# dual_encoder_i2c_revA.net
KiCad netlist of a schematic drawn in EAGLE
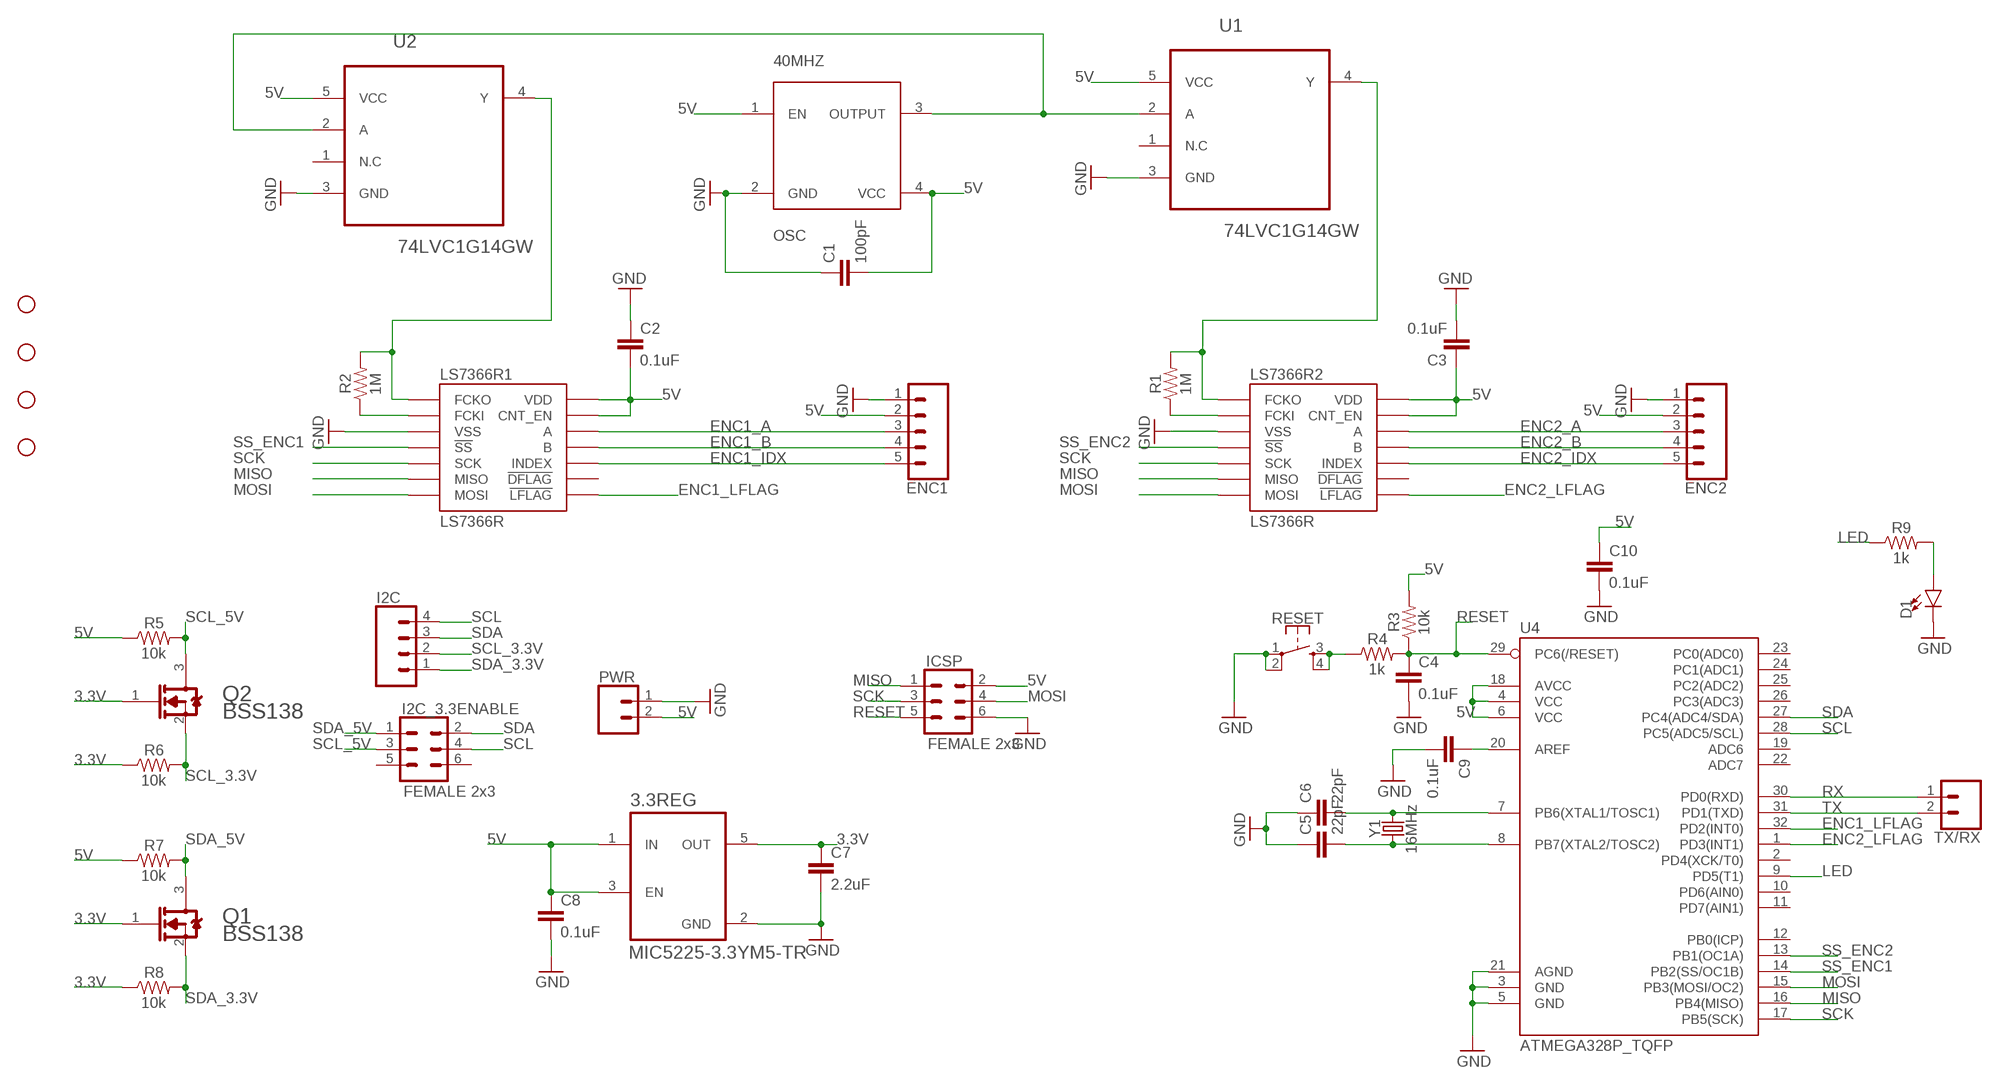
[diagram p0: schematic, sheet 1]

(export (version "E")
  (design (tool "Eeschema 10.0.6"))
  (components
    (comp (ref "3.3REG")
      (value "MIC5225-3.3YM5-TR")
      (footprint "eagle-import:SOT95P280X145-5N")
      (fields (field (name "MF") "Microchip"))
      (libsource (lib "eagle-import") (part "MIC5225-3.3YM5-TR"))
    )
    (comp (ref "40MHZ")
      (value "OSC")
      (footprint "eagle-import:CB3OSCILLATOR")
      (libsource (lib "eagle-import") (part "OSC"))
    )
    (comp (ref "C1")
      (value "100pF")
      (footprint "eagle-import:0603")
      (libsource (lib "eagle-import") (part "100PF-0603-50V-5%"))
    )
    (comp (ref "C2")
      (value "0.1uF")
      (footprint "eagle-import:0603")
      (libsource (lib "eagle-import") (part "0.1UF-0603-25V-5%"))
    )
    (comp (ref "C3")
      (value "0.1uF")
      (footprint "eagle-import:0603")
      (libsource (lib "eagle-import") (part "0.1UF-0603-25V-5%"))
    )
    (comp (ref "C4")
      (value "0.1uF")
      (footprint "eagle-import:0603")
      (libsource (lib "eagle-import") (part "0.1UF-0603-25V-5%"))
    )
    (comp (ref "C5")
      (value "22pF")
      (footprint "eagle-import:0603")
      (libsource (lib "eagle-import") (part "22PF-0603-50V-5%"))
    )
    (comp (ref "C6")
      (value "22pF")
      (footprint "eagle-import:0603")
      (libsource (lib "eagle-import") (part "22PF-0603-50V-5%"))
    )
    (comp (ref "C7")
      (value "2.2uF")
      (footprint "eagle-import:0603")
      (libsource (lib "eagle-import") (part "2.2UF-0603-10V-20%"))
    )
    (comp (ref "C8")
      (value "0.1uF")
      (footprint "eagle-import:0603")
      (libsource (lib "eagle-import") (part "0.1UF-0603-25V-5%"))
    )
    (comp (ref "C9")
      (value "0.1uF")
      (footprint "eagle-import:0603")
      (libsource (lib "eagle-import") (part "0.1UF-0603-25V-5%"))
    )
    (comp (ref "C10")
      (value "0.1uF")
      (footprint "eagle-import:0603")
      (libsource (lib "eagle-import") (part "0.1UF-0603-25V-5%"))
    )
    (comp (ref "D1")
      (value "LED0603")
      (footprint "eagle-import:LED-0603")
      (libsource (lib "eagle-import") (part "LED0603"))
    )
    (comp (ref "ENC1")
      (value "CONN_05")
      (footprint "eagle-import:1X05")
      (libsource (lib "eagle-import") (part "CONN_05"))
    )
    (comp (ref "ENC2")
      (value "CONN_05")
      (footprint "eagle-import:1X05")
      (libsource (lib "eagle-import") (part "CONN_05"))
    )
    (comp (ref "H1")
      (value "STAND-OFF")
      (footprint "eagle-import:STAND-OFF")
      (libsource (lib "eagle-import") (part "STAND-OFF"))
    )
    (comp (ref "H2")
      (value "STAND-OFF")
      (footprint "eagle-import:STAND-OFF")
      (libsource (lib "eagle-import") (part "STAND-OFF"))
    )
    (comp (ref "H3")
      (value "STAND-OFF")
      (footprint "eagle-import:STAND-OFF")
      (libsource (lib "eagle-import") (part "STAND-OFF"))
    )
    (comp (ref "H4")
      (value "STAND-OFF")
      (footprint "eagle-import:STAND-OFF")
      (libsource (lib "eagle-import") (part "STAND-OFF"))
    )
    (comp (ref "I2C")
      (value "CONN_04")
      (footprint "eagle-import:1X04")
      (libsource (lib "eagle-import") (part "CONN_04"))
    )
    (comp (ref "I2C_3.3ENABLE")
      (value "FEMALE 2x3")
      (footprint "eagle-import:2X3")
      (libsource (lib "eagle-import") (part "CONN_03X2FEMALE"))
    )
    (comp (ref "ICSP")
      (value "FEMALE 2x3")
      (footprint "eagle-import:2X3")
      (libsource (lib "eagle-import") (part "CONN_03X2FEMALE"))
    )
    (comp (ref "LS7366R1")
      (value "LS7366R")
      (footprint "eagle-import:SOIC14")
      (fields (field (name "MF") "LSI"))
      (libsource (lib "eagle-import") (part "LS7366R"))
    )
    (comp (ref "LS7366R2")
      (value "LS7366R")
      (footprint "eagle-import:SOIC14")
      (fields (field (name "MF") "LSI"))
      (libsource (lib "eagle-import") (part "LS7366R"))
    )
    (comp (ref "PWR")
      (value "CONN_02-JST-2MM-SMT")
      (footprint "eagle-import:JST-2-SMD")
      (libsource (lib "eagle-import") (part "CONN_02-JST-2MM-SMT"))
    )
    (comp (ref "Q1")
      (value "ON_SEMI_BSS138ON_SEMI_BSS138_0_0")
      (footprint "eagle-import:ON_SEMI_BSS138_0")
      (fields
        (field (name "DIGIKEY_PART_NUMBER") "BSS138CT-ND")
        (field (name "MF") "ON Semi")
        (field (name "MOUSER_PART_NUMBER") "512-BSS138")
      )
      (libsource (lib "eagle-import") (part "ON_SEMI_BSS138ON_SEMI_BSS138_0_0"))
    )
    (comp (ref "Q2")
      (value "ON_SEMI_BSS138ON_SEMI_BSS138_0_0")
      (footprint "eagle-import:ON_SEMI_BSS138_0")
      (fields
        (field (name "DIGIKEY_PART_NUMBER") "BSS138CT-ND")
        (field (name "MF") "ON Semi")
        (field (name "MOUSER_PART_NUMBER") "512-BSS138")
      )
      (libsource (lib "eagle-import") (part "ON_SEMI_BSS138ON_SEMI_BSS138_0_0"))
    )
    (comp (ref "R1")
      (value "1M")
      (footprint "eagle-import:0603")
      (libsource (lib "eagle-import") (part "1MOHM-0603-1/4W-5%"))
    )
    (comp (ref "R2")
      (value "1M")
      (footprint "eagle-import:0603")
      (libsource (lib "eagle-import") (part "1MOHM-0603-1/4W-5%"))
    )
    (comp (ref "R3")
      (value "10k")
      (footprint "eagle-import:0603")
      (libsource (lib "eagle-import") (part "10KOHM-0603-1/10W-1%"))
    )
    (comp (ref "R4")
      (value "1k")
      (footprint "eagle-import:0603")
      (libsource (lib "eagle-import") (part "1KOHM-0603-1/10W-1%"))
    )
    (comp (ref "R5")
      (value "10k")
      (footprint "eagle-import:0603")
      (libsource (lib "eagle-import") (part "10KOHM-0603-1/10W-1%"))
    )
    (comp (ref "R6")
      (value "10k")
      (footprint "eagle-import:0603")
      (libsource (lib "eagle-import") (part "10KOHM-0603-1/10W-1%"))
    )
    (comp (ref "R7")
      (value "10k")
      (footprint "eagle-import:0603")
      (libsource (lib "eagle-import") (part "10KOHM-0603-1/10W-1%"))
    )
    (comp (ref "R8")
      (value "10k")
      (footprint "eagle-import:0603")
      (libsource (lib "eagle-import") (part "10KOHM-0603-1/10W-1%"))
    )
    (comp (ref "R9")
      (value "1k")
      (footprint "eagle-import:0603")
      (libsource (lib "eagle-import") (part "1KOHM-0603-1/10W-1%"))
    )
    (comp (ref "RESET")
      (value "MOMENTARY-SWITCH-SPST-2-SMD-5.2MM")
      (footprint "eagle-import:TACTILE_SWITCH_SMD_5.2MM")
      (libsource (lib "eagle-import") (part "MOMENTARY-SWITCH-SPST-2-SMD-5.2MM"))
    )
    (comp (ref "TX/RX")
      (value "CONN_02")
      (footprint "eagle-import:1X02")
      (libsource (lib "eagle-import") (part "CONN_02"))
    )
    (comp (ref "U1")
      (value "74LVC1G14GW")
      (footprint "eagle-import:SOT65P210X110-5N")
      (fields (field (name "MF") "NXP Semiconductors"))
      (libsource (lib "eagle-import") (part "74LVC1G14GW"))
    )
    (comp (ref "U2")
      (value "74LVC1G14GW")
      (footprint "eagle-import:SOT65P210X110-5N")
      (fields (field (name "MF") "NXP Semiconductors"))
      (libsource (lib "eagle-import") (part "74LVC1G14GW"))
    )
    (comp (ref "U4")
      (value "ATMEGA328P_TQFP")
      (footprint "eagle-import:TQFP32-08")
      (libsource (lib "eagle-import") (part "ATMEGA328P_TQFP"))
    )
    (comp (ref "Y1")
      (value "16MHz")
      (footprint "eagle-import:HC49US")
      (libsource (lib "eagle-import") (part "CRYSTAL-16MHZPTH-HC49US"))
    )
  )
  (nets
    (net (code "1") (name "/3.3V") (class "Default")
      (node (ref "3.3REG") (pin "5") (pinfunction "OUT_5") (pintype "output"))
      (node (ref "C7") (pin "1") (pinfunction "1_1") (pintype "passive"))
      (node (ref "Q1") (pin "1") (pinfunction "G_1") (pintype "bidirectional"))
      (node (ref "Q2") (pin "1") (pinfunction "G_1") (pintype "bidirectional"))
      (node (ref "R6") (pin "1") (pinfunction "1_1") (pintype "passive"))
      (node (ref "R8") (pin "1") (pinfunction "1_1") (pintype "passive"))
    )
    (net (code "2") (name "/5V") (class "Default")
      (node (ref "3.3REG") (pin "1") (pinfunction "IN_1") (pintype "input"))
      (node (ref "3.3REG") (pin "3") (pinfunction "EN_3") (pintype "input"))
      (node (ref "40MHZ") (pin "1") (pinfunction "EN_1") (pintype "input"))
      (node (ref "40MHZ") (pin "4") (pinfunction "VCC_4") (pintype "input"))
      (node (ref "C1") (pin "2") (pinfunction "2_2") (pintype "passive"))
      (node (ref "C10") (pin "1") (pinfunction "1_1") (pintype "passive"))
      (node (ref "C2") (pin "2") (pinfunction "2_2") (pintype "passive"))
      (node (ref "C3") (pin "1") (pinfunction "1_1") (pintype "passive"))
      (node (ref "C8") (pin "1") (pinfunction "1_1") (pintype "passive"))
      (node (ref "ENC1") (pin "2") (pinfunction "2_2") (pintype "passive"))
      (node (ref "ENC2") (pin "2") (pinfunction "2_2") (pintype "passive"))
      (node (ref "ICSP") (pin "2") (pinfunction "2_2") (pintype "bidirectional"))
      (node (ref "LS7366R1") (pin "13") (pinfunction "CNT_EN_13") (pintype "bidirectional"))
      (node (ref "LS7366R1") (pin "14") (pinfunction "VDD_14") (pintype "bidirectional"))
      (node (ref "LS7366R2") (pin "13") (pinfunction "CNT_EN_13") (pintype "bidirectional"))
      (node (ref "LS7366R2") (pin "14") (pinfunction "VDD_14") (pintype "bidirectional"))
      (node (ref "PWR") (pin "2") (pinfunction "1_2") (pintype "passive"))
      (node (ref "R3") (pin "2") (pinfunction "2_2") (pintype "passive"))
      (node (ref "R5") (pin "1") (pinfunction "1_1") (pintype "passive"))
      (node (ref "R7") (pin "1") (pinfunction "1_1") (pintype "passive"))
      (node (ref "U1") (pin "5") (pinfunction "VCC_5") (pintype "power_in"))
      (node (ref "U2") (pin "5") (pinfunction "VCC_5") (pintype "power_in"))
      (node (ref "U4") (pin "18") (pinfunction "AVCC_18") (pintype "bidirectional"))
      (node (ref "U4") (pin "4") (pinfunction "VCC_4") (pintype "bidirectional"))
      (node (ref "U4") (pin "6") (pinfunction "VCC_6") (pintype "bidirectional"))
    )
    (net (code "3") (name "/ENC1_A") (class "Default")
      (node (ref "ENC1") (pin "3") (pinfunction "3_3") (pintype "passive"))
      (node (ref "LS7366R1") (pin "12") (pinfunction "A_12") (pintype "bidirectional"))
    )
    (net (code "4") (name "/ENC1_B") (class "Default")
      (node (ref "ENC1") (pin "4") (pinfunction "4_4") (pintype "passive"))
      (node (ref "LS7366R1") (pin "11") (pinfunction "B_11") (pintype "bidirectional"))
    )
    (net (code "5") (name "/ENC1_IDX") (class "Default")
      (node (ref "ENC1") (pin "5") (pinfunction "5_5") (pintype "passive"))
      (node (ref "LS7366R1") (pin "10") (pinfunction "INDEX_10") (pintype "bidirectional"))
    )
    (net (code "6") (name "/ENC1_LFLAG") (class "Default")
      (node (ref "LS7366R1") (pin "8") (pinfunction "~{LFLAG}_8") (pintype "bidirectional"))
      (node (ref "U4") (pin "32") (pinfunction "PD2(INT0)_32") (pintype "bidirectional"))
    )
    (net (code "7") (name "/ENC2_A") (class "Default")
      (node (ref "ENC2") (pin "3") (pinfunction "3_3") (pintype "passive"))
      (node (ref "LS7366R2") (pin "12") (pinfunction "A_12") (pintype "bidirectional"))
    )
    (net (code "8") (name "/ENC2_B") (class "Default")
      (node (ref "ENC2") (pin "4") (pinfunction "4_4") (pintype "passive"))
      (node (ref "LS7366R2") (pin "11") (pinfunction "B_11") (pintype "bidirectional"))
    )
    (net (code "9") (name "/ENC2_IDX") (class "Default")
      (node (ref "ENC2") (pin "5") (pinfunction "5_5") (pintype "passive"))
      (node (ref "LS7366R2") (pin "10") (pinfunction "INDEX_10") (pintype "bidirectional"))
    )
    (net (code "10") (name "/ENC2_LFLAG") (class "Default")
      (node (ref "LS7366R2") (pin "8") (pinfunction "~{LFLAG}_8") (pintype "bidirectional"))
      (node (ref "U4") (pin "1") (pinfunction "PD3(INT1)_1") (pintype "bidirectional"))
    )
    (net (code "11") (name "/LED") (class "Default")
      (node (ref "R9") (pin "1") (pinfunction "1_1") (pintype "passive"))
      (node (ref "U4") (pin "9") (pinfunction "PD5(T1)_9") (pintype "bidirectional"))
    )
    (net (code "12") (name "/MISO") (class "Default")
      (node (ref "ICSP") (pin "1") (pinfunction "1_1") (pintype "bidirectional"))
      (node (ref "LS7366R1") (pin "6") (pinfunction "MISO_6") (pintype "bidirectional"))
      (node (ref "LS7366R2") (pin "6") (pinfunction "MISO_6") (pintype "bidirectional"))
      (node (ref "U4") (pin "16") (pinfunction "PB4(MISO)_16") (pintype "bidirectional"))
    )
    (net (code "13") (name "/MOSI") (class "Default")
      (node (ref "ICSP") (pin "4") (pinfunction "4_4") (pintype "bidirectional"))
      (node (ref "LS7366R1") (pin "7") (pinfunction "MOSI_7") (pintype "bidirectional"))
      (node (ref "LS7366R2") (pin "7") (pinfunction "MOSI_7") (pintype "bidirectional"))
      (node (ref "U4") (pin "15") (pinfunction "PB3(MOSI/OC2)_15") (pintype "bidirectional"))
    )
    (net (code "14") (name "/RESET") (class "Default")
      (node (ref "C4") (pin "1") (pinfunction "1_1") (pintype "passive"))
      (node (ref "ICSP") (pin "5") (pinfunction "5_5") (pintype "bidirectional"))
      (node (ref "R3") (pin "1") (pinfunction "1_1") (pintype "passive"))
      (node (ref "R4") (pin "2") (pinfunction "2_2") (pintype "passive"))
      (node (ref "U4") (pin "29") (pinfunction "PC6(/RESET)_29") (pintype "bidirectional"))
    )
    (net (code "15") (name "/RX") (class "Default")
      (node (ref "TX/RX") (pin "1") (pinfunction "1_1") (pintype "passive"))
      (node (ref "U4") (pin "30") (pinfunction "PD0(RXD)_30") (pintype "bidirectional"))
    )
    (net (code "16") (name "/SCK") (class "Default")
      (node (ref "ICSP") (pin "3") (pinfunction "3_3") (pintype "bidirectional"))
      (node (ref "LS7366R1") (pin "5") (pinfunction "SCK_5") (pintype "bidirectional"))
      (node (ref "LS7366R2") (pin "5") (pinfunction "SCK_5") (pintype "bidirectional"))
      (node (ref "U4") (pin "17") (pinfunction "PB5(SCK)_17") (pintype "bidirectional"))
    )
    (net (code "17") (name "/SCL") (class "Default")
      (node (ref "I2C") (pin "4") (pinfunction "4_4") (pintype "passive"))
      (node (ref "I2C_3.3ENABLE") (pin "4") (pinfunction "4_4") (pintype "bidirectional"))
      (node (ref "U4") (pin "28") (pinfunction "PC5(ADC5/SCL)_28") (pintype "bidirectional"))
    )
    (net (code "18") (name "/SCL_3.3V") (class "Default")
      (node (ref "I2C") (pin "2") (pinfunction "2_2") (pintype "passive"))
      (node (ref "Q2") (pin "2") (pinfunction "S_2") (pintype "bidirectional"))
      (node (ref "R6") (pin "2") (pinfunction "2_2") (pintype "passive"))
    )
    (net (code "19") (name "/SCL_5V") (class "Default")
      (node (ref "I2C_3.3ENABLE") (pin "3") (pinfunction "3_3") (pintype "bidirectional"))
      (node (ref "Q2") (pin "3") (pinfunction "D_3") (pintype "bidirectional"))
      (node (ref "R5") (pin "2") (pinfunction "2_2") (pintype "passive"))
    )
    (net (code "20") (name "/SDA") (class "Default")
      (node (ref "I2C") (pin "3") (pinfunction "3_3") (pintype "passive"))
      (node (ref "I2C_3.3ENABLE") (pin "2") (pinfunction "2_2") (pintype "bidirectional"))
      (node (ref "U4") (pin "27") (pinfunction "PC4(ADC4/SDA)_27") (pintype "bidirectional"))
    )
    (net (code "21") (name "/SDA_3.3V") (class "Default")
      (node (ref "I2C") (pin "1") (pinfunction "1_1") (pintype "passive"))
      (node (ref "Q1") (pin "2") (pinfunction "S_2") (pintype "bidirectional"))
      (node (ref "R8") (pin "2") (pinfunction "2_2") (pintype "passive"))
    )
    (net (code "22") (name "/SDA_5V") (class "Default")
      (node (ref "I2C_3.3ENABLE") (pin "1") (pinfunction "1_1") (pintype "bidirectional"))
      (node (ref "Q1") (pin "3") (pinfunction "D_3") (pintype "bidirectional"))
      (node (ref "R7") (pin "2") (pinfunction "2_2") (pintype "passive"))
    )
    (net (code "23") (name "/SS_ENC1") (class "Default")
      (node (ref "LS7366R1") (pin "4") (pinfunction "~{SS}_4") (pintype "bidirectional"))
      (node (ref "U4") (pin "14") (pinfunction "PB2(SS/OC1B)_14") (pintype "bidirectional"))
    )
    (net (code "24") (name "/SS_ENC2") (class "Default")
      (node (ref "LS7366R2") (pin "4") (pinfunction "~{SS}_4") (pintype "bidirectional"))
      (node (ref "U4") (pin "13") (pinfunction "PB1(OC1A)_13") (pintype "bidirectional"))
    )
    (net (code "25") (name "/TX") (class "Default")
      (node (ref "TX/RX") (pin "2") (pinfunction "2_2") (pintype "passive"))
      (node (ref "U4") (pin "31") (pinfunction "PD1(TXD)_31") (pintype "bidirectional"))
    )
    (net (code "26") (name "GND") (class "Default")
      (node (ref "3.3REG") (pin "2") (pinfunction "GND_2") (pintype "power_in"))
      (node (ref "40MHZ") (pin "2") (pinfunction "GND_2") (pintype "input"))
      (node (ref "C1") (pin "1") (pinfunction "1_1") (pintype "passive"))
      (node (ref "C10") (pin "2") (pinfunction "2_2") (pintype "passive"))
      (node (ref "C2") (pin "1") (pinfunction "1_1") (pintype "passive"))
      (node (ref "C3") (pin "2") (pinfunction "2_2") (pintype "passive"))
      (node (ref "C4") (pin "2") (pinfunction "2_2") (pintype "passive"))
      (node (ref "C5") (pin "1") (pinfunction "1_1") (pintype "passive"))
      (node (ref "C6") (pin "1") (pinfunction "1_1") (pintype "passive"))
      (node (ref "C7") (pin "2") (pinfunction "2_2") (pintype "passive"))
      (node (ref "C8") (pin "2") (pinfunction "2_2") (pintype "passive"))
      (node (ref "C9") (pin "2") (pinfunction "2_2") (pintype "passive"))
      (node (ref "D1") (pin "C") (pinfunction "C_C") (pintype "passive"))
      (node (ref "ENC1") (pin "1") (pinfunction "1_1") (pintype "passive"))
      (node (ref "ENC2") (pin "1") (pinfunction "1_1") (pintype "passive"))
      (node (ref "ICSP") (pin "6") (pinfunction "6_6") (pintype "bidirectional"))
      (node (ref "LS7366R1") (pin "3") (pinfunction "VSS_3") (pintype "bidirectional"))
      (node (ref "LS7366R2") (pin "3") (pinfunction "VSS_3") (pintype "bidirectional"))
      (node (ref "PWR") (pin "1") (pinfunction "2_1") (pintype "passive"))
      (node (ref "RESET") (pin "1") (pinfunction "1_1") (pintype "passive"))
      (node (ref "RESET") (pin "2") (pinfunction "2_2") (pintype "passive"))
      (node (ref "U1") (pin "3") (pinfunction "GND_3") (pintype "passive"))
      (node (ref "U2") (pin "3") (pinfunction "GND_3") (pintype "passive"))
      (node (ref "U4") (pin "21") (pinfunction "AGND_21") (pintype "bidirectional"))
      (node (ref "U4") (pin "3") (pinfunction "GND_3") (pintype "bidirectional"))
      (node (ref "U4") (pin "5") (pinfunction "GND_5") (pintype "bidirectional"))
    )
    (net (code "27") (name "Net-(40MHZ-OUTPUT)") (class "Default")
      (node (ref "40MHZ") (pin "3") (pinfunction "OUTPUT_3") (pintype "output"))
      (node (ref "U1") (pin "2") (pinfunction "A_2") (pintype "input"))
      (node (ref "U2") (pin "2") (pinfunction "A_2") (pintype "input"))
    )
    (net (code "28") (name "Net-(D1-PadA)") (class "Default")
      (node (ref "D1") (pin "A") (pinfunction "A_A") (pintype "passive"))
      (node (ref "R9") (pin "2") (pinfunction "2_2") (pintype "passive"))
    )
    (net (code "29") (name "Net-(LS7366R1-FCKI)") (class "Default")
      (node (ref "LS7366R1") (pin "2") (pinfunction "FCKI_2") (pintype "bidirectional"))
      (node (ref "R2") (pin "1") (pinfunction "1_1") (pintype "passive"))
    )
    (net (code "30") (name "Net-(LS7366R1-FCKO)") (class "Default")
      (node (ref "LS7366R1") (pin "1") (pinfunction "FCKO_1") (pintype "bidirectional"))
      (node (ref "R2") (pin "2") (pinfunction "2_2") (pintype "passive"))
      (node (ref "U2") (pin "4") (pinfunction "Y_4") (pintype "output"))
    )
    (net (code "31") (name "Net-(LS7366R2-FCKI)") (class "Default")
      (node (ref "LS7366R2") (pin "2") (pinfunction "FCKI_2") (pintype "bidirectional"))
      (node (ref "R1") (pin "1") (pinfunction "1_1") (pintype "passive"))
    )
    (net (code "32") (name "Net-(LS7366R2-FCKO)") (class "Default")
      (node (ref "LS7366R2") (pin "1") (pinfunction "FCKO_1") (pintype "bidirectional"))
      (node (ref "R1") (pin "2") (pinfunction "2_2") (pintype "passive"))
      (node (ref "U1") (pin "4") (pinfunction "Y_4") (pintype "output"))
    )
    (net (code "33") (name "Net-(R4-Pad1)") (class "Default")
      (node (ref "R4") (pin "1") (pinfunction "1_1") (pintype "passive"))
      (node (ref "RESET") (pin "3") (pinfunction "3_3") (pintype "passive"))
      (node (ref "RESET") (pin "4") (pinfunction "4_4") (pintype "passive"))
    )
    (net (code "34") (name "Net-(U4-AREF)") (class "Default")
      (node (ref "C9") (pin "1") (pinfunction "1_1") (pintype "passive"))
      (node (ref "U4") (pin "20") (pinfunction "AREF_20") (pintype "bidirectional"))
    )
    (net (code "35") (name "Net-(U4-PB6(XTAL1{slash}TOSC1))") (class "Default")
      (node (ref "C6") (pin "2") (pinfunction "2_2") (pintype "passive"))
      (node (ref "U4") (pin "7") (pinfunction "PB6(XTAL1/TOSC1)_7") (pintype "bidirectional"))
      (node (ref "Y1") (pin "2") (pinfunction "2_2") (pintype "passive"))
    )
    (net (code "36") (name "Net-(U4-PB7(XTAL2{slash}TOSC2))") (class "Default")
      (node (ref "C5") (pin "2") (pinfunction "2_2") (pintype "passive"))
      (node (ref "U4") (pin "8") (pinfunction "PB7(XTAL2/TOSC2)_8") (pintype "bidirectional"))
      (node (ref "Y1") (pin "1") (pinfunction "1_1") (pintype "passive"))
    )
    (net (code "37") (name "unconnected-(I2C_3.3ENABLE-Pad5)") (class "Default")
      (node (ref "I2C_3.3ENABLE") (pin "5") (pinfunction "5_5") (pintype "bidirectional"))
    )
    (net (code "38") (name "unconnected-(I2C_3.3ENABLE-Pad6)") (class "Default")
      (node (ref "I2C_3.3ENABLE") (pin "6") (pinfunction "6_6") (pintype "bidirectional"))
    )
    (net (code "39") (name "unconnected-(LS7366R1-~{DFLAG}-Pad9)") (class "Default")
      (node (ref "LS7366R1") (pin "9") (pinfunction "~{DFLAG}_9") (pintype "bidirectional"))
    )
    (net (code "40") (name "unconnected-(LS7366R2-~{DFLAG}-Pad9)") (class "Default")
      (node (ref "LS7366R2") (pin "9") (pinfunction "~{DFLAG}_9") (pintype "bidirectional"))
    )
    (net (code "41") (name "unconnected-(U1-N.C-Pad1)") (class "Default")
      (node (ref "U1") (pin "1") (pinfunction "N.C_1") (pintype "no_connect"))
    )
    (net (code "42") (name "unconnected-(U2-N.C-Pad1)") (class "Default")
      (node (ref "U2") (pin "1") (pinfunction "N.C_1") (pintype "no_connect"))
    )
    (net (code "43") (name "unconnected-(U4-ADC6-Pad19)") (class "Default")
      (node (ref "U4") (pin "19") (pinfunction "ADC6_19") (pintype "bidirectional"))
    )
    (net (code "44") (name "unconnected-(U4-ADC7-Pad22)") (class "Default")
      (node (ref "U4") (pin "22") (pinfunction "ADC7_22") (pintype "bidirectional"))
    )
    (net (code "45") (name "unconnected-(U4-PB0(ICP)-Pad12)") (class "Default")
      (node (ref "U4") (pin "12") (pinfunction "PB0(ICP)_12") (pintype "bidirectional"))
    )
    (net (code "46") (name "unconnected-(U4-PC0(ADC0)-Pad23)") (class "Default")
      (node (ref "U4") (pin "23") (pinfunction "PC0(ADC0)_23") (pintype "bidirectional"))
    )
    (net (code "47") (name "unconnected-(U4-PC1(ADC1)-Pad24)") (class "Default")
      (node (ref "U4") (pin "24") (pinfunction "PC1(ADC1)_24") (pintype "bidirectional"))
    )
    (net (code "48") (name "unconnected-(U4-PC2(ADC2)-Pad25)") (class "Default")
      (node (ref "U4") (pin "25") (pinfunction "PC2(ADC2)_25") (pintype "bidirectional"))
    )
    (net (code "49") (name "unconnected-(U4-PC3(ADC3)-Pad26)") (class "Default")
      (node (ref "U4") (pin "26") (pinfunction "PC3(ADC3)_26") (pintype "bidirectional"))
    )
    (net (code "50") (name "unconnected-(U4-PD4(XCK{slash}T0)-Pad2)") (class "Default")
      (node (ref "U4") (pin "2") (pinfunction "PD4(XCK/T0)_2") (pintype "bidirectional"))
    )
    (net (code "51") (name "unconnected-(U4-PD6(AIN0)-Pad10)") (class "Default")
      (node (ref "U4") (pin "10") (pinfunction "PD6(AIN0)_10") (pintype "bidirectional"))
    )
    (net (code "52") (name "unconnected-(U4-PD7(AIN1)-Pad11)") (class "Default")
      (node (ref "U4") (pin "11") (pinfunction "PD7(AIN1)_11") (pintype "bidirectional"))
    )
  )
)
